# GpsTracker_v1_0.net
KiCad netlist of a schematic drawn in EAGLE
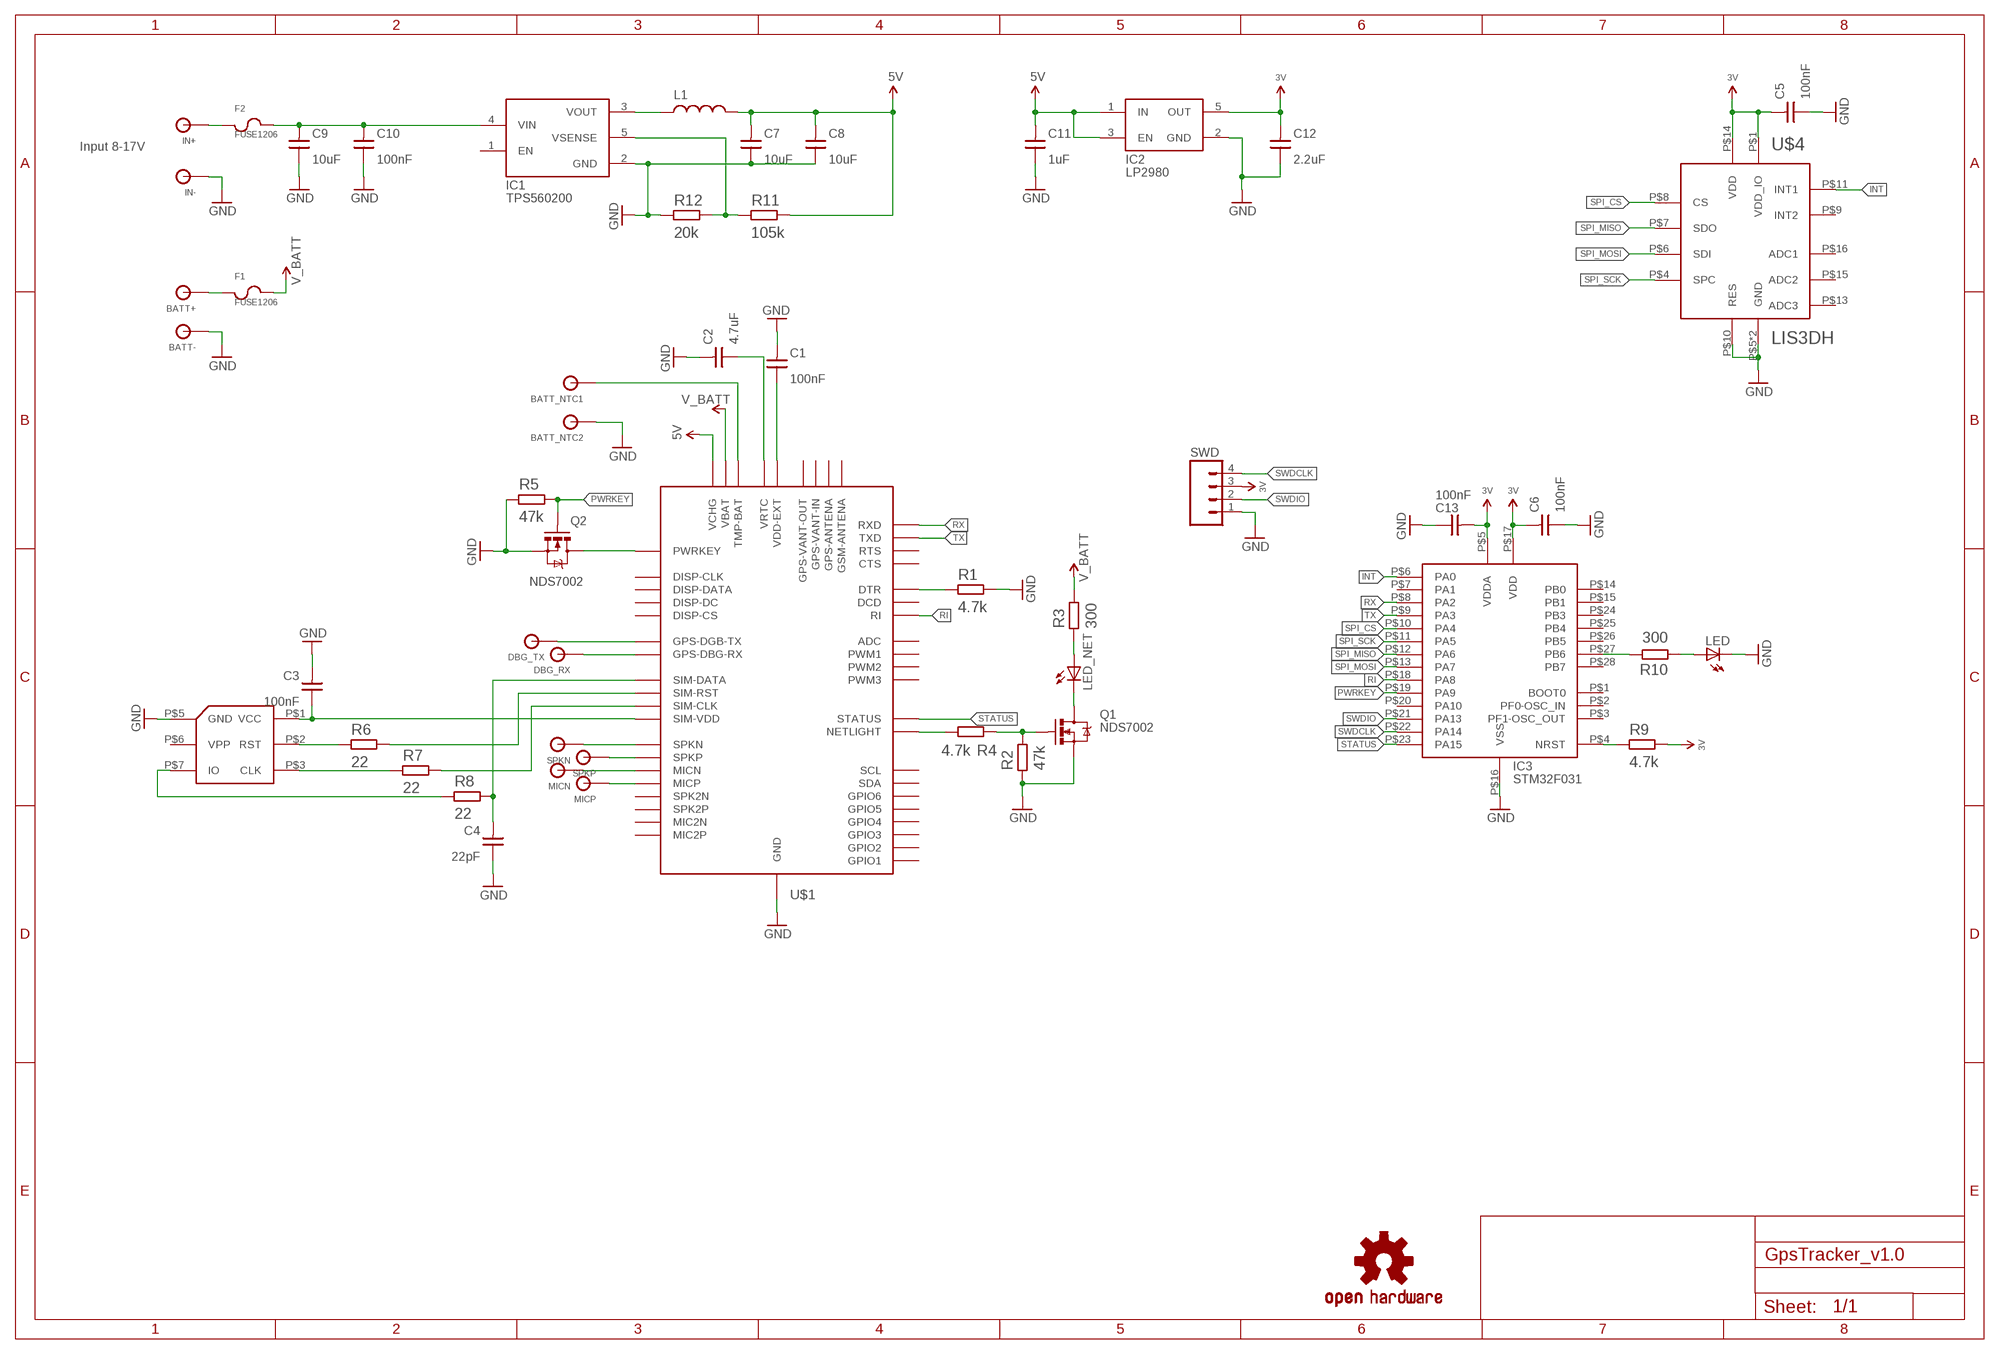
[diagram p0: schematic, sheet 1]

(export (version "E")
  (design (tool "Eeschema 10.0.6"))
  (components
    (comp (ref "BATT+")
      (value "TEST_POINT_SMD")
      (footprint "eagle-import:TEST_POINT_SMD")
      (libsource (lib "eagle-import") (part "TEST_POINT_SMD"))
    )
    (comp (ref "BATT-")
      (value "TEST_POINT_SMD")
      (footprint "eagle-import:TEST_POINT_SMD")
      (libsource (lib "eagle-import") (part "TEST_POINT_SMD"))
    )
    (comp (ref "BATT_NTC1")
      (value "TEST_POINT_R04")
      (footprint "eagle-import:TP_R04")
      (libsource (lib "eagle-import") (part "TEST_POINT_R04"))
    )
    (comp (ref "BATT_NTC2")
      (value "TEST_POINT_R04")
      (footprint "eagle-import:TP_R04")
      (libsource (lib "eagle-import") (part "TEST_POINT_R04"))
    )
    (comp (ref "C1")
      (value "100nF")
      (footprint "eagle-import:R0603")
      (libsource (lib "eagle-import") (part "C0603"))
    )
    (comp (ref "C2")
      (value "4.7uF")
      (footprint "eagle-import:R0805")
      (libsource (lib "eagle-import") (part "C0805"))
    )
    (comp (ref "C3")
      (value "100nF")
      (footprint "eagle-import:R0603")
      (libsource (lib "eagle-import") (part "C0603"))
    )
    (comp (ref "C4")
      (value "22pF")
      (footprint "eagle-import:R0603")
      (libsource (lib "eagle-import") (part "C0603"))
    )
    (comp (ref "C5")
      (value "100nF")
      (footprint "eagle-import:R0603")
      (libsource (lib "eagle-import") (part "C0603"))
    )
    (comp (ref "C6")
      (value "100nF")
      (footprint "eagle-import:R0603")
      (libsource (lib "eagle-import") (part "C0603"))
    )
    (comp (ref "C7")
      (value "10uF")
      (footprint "eagle-import:R0805")
      (libsource (lib "eagle-import") (part "C0805"))
    )
    (comp (ref "C8")
      (value "10uF")
      (footprint "eagle-import:R0805")
      (libsource (lib "eagle-import") (part "C0805"))
    )
    (comp (ref "C9")
      (value "10uF")
      (footprint "eagle-import:1206")
      (libsource (lib "eagle-import") (part "C1206"))
    )
    (comp (ref "C10")
      (value "100nF")
      (footprint "eagle-import:R0603")
      (libsource (lib "eagle-import") (part "C0603"))
    )
    (comp (ref "C11")
      (value "1uF")
      (footprint "eagle-import:R0805")
      (libsource (lib "eagle-import") (part "C0805"))
    )
    (comp (ref "C12")
      (value "2.2uF")
      (footprint "eagle-import:R0805")
      (libsource (lib "eagle-import") (part "C0805"))
    )
    (comp (ref "C13")
      (value "100nF")
      (footprint "eagle-import:R0603")
      (libsource (lib "eagle-import") (part "C0603"))
    )
    (comp (ref "DBG_RX")
      (value "TEST_POINT_R04")
      (footprint "eagle-import:TP_R04")
      (libsource (lib "eagle-import") (part "TEST_POINT_R04"))
    )
    (comp (ref "DBG_TX")
      (value "TEST_POINT_R04")
      (footprint "eagle-import:TP_R04")
      (libsource (lib "eagle-import") (part "TEST_POINT_R04"))
    )
    (comp (ref "F1")
      (value "FUSE1206")
      (footprint "eagle-import:1206")
      (libsource (lib "eagle-import") (part "FUSE1206"))
    )
    (comp (ref "F2")
      (value "FUSE1206")
      (footprint "eagle-import:1206")
      (libsource (lib "eagle-import") (part "FUSE1206"))
    )
    (comp (ref "IC1")
      (value "TPS560200")
      (footprint "eagle-import:SOT23-5L")
      (libsource (lib "eagle-import") (part "TPS560200"))
    )
    (comp (ref "IC2")
      (value "LP2980")
      (footprint "eagle-import:SOT23-5L")
      (libsource (lib "eagle-import") (part "LP2980"))
    )
    (comp (ref "IC3")
      (value "STM32F031")
      (footprint "eagle-import:UFQFPN28")
      (libsource (lib "eagle-import") (part "STM32F031"))
    )
    (comp (ref "IN+")
      (value "TEST_POINT_SMD")
      (footprint "eagle-import:TEST_POINT_SMD")
      (libsource (lib "eagle-import") (part "TEST_POINT_SMD"))
    )
    (comp (ref "IN-")
      (value "TEST_POINT_SMD")
      (footprint "eagle-import:TEST_POINT_SMD")
      (libsource (lib "eagle-import") (part "TEST_POINT_SMD"))
    )
    (comp (ref "L1")
      (value "LNRG_4026")
      (footprint "eagle-import:NRG_4026")
      (libsource (lib "eagle-import") (part "LNRG_4026"))
    )
    (comp (ref "LED")
      (value "LED0603")
      (footprint "eagle-import:LED-0603")
      (libsource (lib "eagle-import") (part "LED0603"))
    )
    (comp (ref "LED_NET")
      (value "LED0603")
      (footprint "eagle-import:LED-0603")
      (libsource (lib "eagle-import") (part "LED0603"))
    )
    (comp (ref "LOGO1")
      (value "OSHW-LOGOS")
      (footprint "eagle-import:OSHW-LOGO-S")
      (libsource (lib "eagle-import") (part "OSHW-LOGOS"))
    )
    (comp (ref "MICN")
      (value "TEST_POINT_R04")
      (footprint "eagle-import:TP_R04")
      (libsource (lib "eagle-import") (part "TEST_POINT_R04"))
    )
    (comp (ref "MICP")
      (value "TEST_POINT_R04")
      (footprint "eagle-import:TP_R04")
      (libsource (lib "eagle-import") (part "TEST_POINT_R04"))
    )
    (comp (ref "Q1")
      (value "NDS7002")
      (footprint "eagle-import:SOT23")
      (libsource (lib "eagle-import") (part "NDS7002"))
    )
    (comp (ref "Q2")
      (value "NDS7002")
      (footprint "eagle-import:SOT23")
      (libsource (lib "eagle-import") (part "NDS7002"))
    )
    (comp (ref "R1")
      (value "4.7k")
      (footprint "eagle-import:R0603")
      (libsource (lib "eagle-import") (part "R0603"))
    )
    (comp (ref "R2")
      (value "47k")
      (footprint "eagle-import:R0603")
      (libsource (lib "eagle-import") (part "R0603"))
    )
    (comp (ref "R3")
      (value "300")
      (footprint "eagle-import:R0603")
      (libsource (lib "eagle-import") (part "R0603"))
    )
    (comp (ref "R4")
      (value "4.7k")
      (footprint "eagle-import:R0603")
      (libsource (lib "eagle-import") (part "R0603"))
    )
    (comp (ref "R5")
      (value "47k")
      (footprint "eagle-import:R0603")
      (libsource (lib "eagle-import") (part "R0603"))
    )
    (comp (ref "R6")
      (value "22")
      (footprint "eagle-import:R0603")
      (libsource (lib "eagle-import") (part "R0603"))
    )
    (comp (ref "R7")
      (value "22")
      (footprint "eagle-import:R0603")
      (libsource (lib "eagle-import") (part "R0603"))
    )
    (comp (ref "R8")
      (value "22")
      (footprint "eagle-import:R0603")
      (libsource (lib "eagle-import") (part "R0603"))
    )
    (comp (ref "R9")
      (value "4.7k")
      (footprint "eagle-import:R0603")
      (libsource (lib "eagle-import") (part "R0603"))
    )
    (comp (ref "R10")
      (value "300")
      (footprint "eagle-import:R0603")
      (libsource (lib "eagle-import") (part "R0603"))
    )
    (comp (ref "R11")
      (value "105k")
      (footprint "eagle-import:R0603")
      (libsource (lib "eagle-import") (part "R0603"))
    )
    (comp (ref "R12")
      (value "20k")
      (footprint "eagle-import:R0603")
      (libsource (lib "eagle-import") (part "R0603"))
    )
    (comp (ref "SPKN")
      (value "TEST_POINT_R04")
      (footprint "eagle-import:TP_R04")
      (libsource (lib "eagle-import") (part "TEST_POINT_R04"))
    )
    (comp (ref "SPKP")
      (value "TEST_POINT_R04")
      (footprint "eagle-import:TP_R04")
      (libsource (lib "eagle-import") (part "TEST_POINT_R04"))
    )
    (comp (ref "SWD")
      (value "M041.27MM")
      (footprint "eagle-import:1X04-1.27MM")
      (libsource (lib "eagle-import") (part "M041.27MM"))
    )
    (comp (ref "U$1")
      (value "SIM908")
      (footprint "eagle-import:SIM908")
      (libsource (lib "eagle-import") (part "SIM908"))
    )
    (comp (ref "U$3")
      (value "SIM_CARD")
      (footprint "eagle-import:SIM_SAMSUNG")
      (libsource (lib "eagle-import") (part "SIM_CARD"))
    )
    (comp (ref "U$4")
      (value "LIS3DH")
      (footprint "eagle-import:LGA16D")
      (libsource (lib "eagle-import") (part "LIS3DH"))
    )
  )
  (nets
    (net (code "1") (name "3V") (class "Default")
      (node (ref "C12") (pin "2") (pinfunction "2_2") (pintype "bidirectional"))
      (node (ref "C13") (pin "2") (pinfunction "2_2") (pintype "bidirectional"))
      (node (ref "C5") (pin "2") (pinfunction "2_2") (pintype "bidirectional"))
      (node (ref "C6") (pin "2") (pinfunction "2_2") (pintype "bidirectional"))
      (node (ref "IC2") (pin "5") (pinfunction "OUT_5") (pintype "bidirectional"))
      (node (ref "IC3") (pin "P$17") (pinfunction "VDD_P$17") (pintype "bidirectional"))
      (node (ref "IC3") (pin "P$5") (pinfunction "VDDA_P$5") (pintype "bidirectional"))
      (node (ref "R9") (pin "2") (pinfunction "2_2") (pintype "bidirectional"))
      (node (ref "SWD") (pin "3") (pinfunction "3_3") (pintype "passive"))
      (node (ref "U$4") (pin "P$1") (pinfunction "VDD_IO_P$1") (pintype "bidirectional"))
      (node (ref "U$4") (pin "P$14") (pinfunction "VDD_P$14") (pintype "bidirectional"))
    )
    (net (code "2") (name "5V") (class "Default")
      (node (ref "C11") (pin "2") (pinfunction "2_2") (pintype "bidirectional"))
      (node (ref "C7") (pin "2") (pinfunction "2_2") (pintype "bidirectional"))
      (node (ref "C8") (pin "2") (pinfunction "2_2") (pintype "bidirectional"))
      (node (ref "IC2") (pin "1") (pinfunction "IN_1") (pintype "bidirectional"))
      (node (ref "IC2") (pin "3") (pinfunction "EN_3") (pintype "bidirectional"))
      (node (ref "L1") (pin "P$2") (pinfunction "2_P$2") (pintype "bidirectional"))
      (node (ref "R11") (pin "2") (pinfunction "2_2") (pintype "bidirectional"))
      (node (ref "U$1") (pin "VCHG") (pinfunction "VCHG_VCHG") (pintype "bidirectional"))
    )
    (net (code "3") (name "GND") (class "Default")
      (node (ref "BATT-") (pin "P$1") (pinfunction "P$1_P$1") (pintype "bidirectional"))
      (node (ref "BATT_NTC2") (pin "P$1") (pinfunction "P$1_P$1") (pintype "bidirectional"))
      (node (ref "C1") (pin "2") (pinfunction "2_2") (pintype "bidirectional"))
      (node (ref "C10") (pin "1") (pinfunction "1_1") (pintype "bidirectional"))
      (node (ref "C11") (pin "1") (pinfunction "1_1") (pintype "bidirectional"))
      (node (ref "C12") (pin "1") (pinfunction "1_1") (pintype "bidirectional"))
      (node (ref "C13") (pin "1") (pinfunction "1_1") (pintype "bidirectional"))
      (node (ref "C2") (pin "2") (pinfunction "2_2") (pintype "bidirectional"))
      (node (ref "C3") (pin "2") (pinfunction "2_2") (pintype "bidirectional"))
      (node (ref "C4") (pin "1") (pinfunction "1_1") (pintype "bidirectional"))
      (node (ref "C5") (pin "1") (pinfunction "1_1") (pintype "bidirectional"))
      (node (ref "C6") (pin "1") (pinfunction "1_1") (pintype "bidirectional"))
      (node (ref "C7") (pin "1") (pinfunction "1_1") (pintype "bidirectional"))
      (node (ref "C8") (pin "1") (pinfunction "1_1") (pintype "bidirectional"))
      (node (ref "C9") (pin "1") (pinfunction "1_1") (pintype "bidirectional"))
      (node (ref "IC1") (pin "2") (pinfunction "GND_2") (pintype "bidirectional"))
      (node (ref "IC2") (pin "2") (pinfunction "GND_2") (pintype "bidirectional"))
      (node (ref "IC3") (pin "P$16") (pinfunction "VSS_P$16") (pintype "bidirectional"))
      (node (ref "IN-") (pin "P$1") (pinfunction "P$1_P$1") (pintype "bidirectional"))
      (node (ref "LED") (pin "C") (pinfunction "C_C") (pintype "passive"))
      (node (ref "Q1") (pin "2") (pinfunction "S_2") (pintype "passive"))
      (node (ref "Q2") (pin "2") (pinfunction "S_2") (pintype "passive"))
      (node (ref "R1") (pin "2") (pinfunction "2_2") (pintype "bidirectional"))
      (node (ref "R12") (pin "1") (pinfunction "1_1") (pintype "bidirectional"))
      (node (ref "R2") (pin "1") (pinfunction "1_1") (pintype "bidirectional"))
      (node (ref "R5") (pin "1") (pinfunction "1_1") (pintype "bidirectional"))
      (node (ref "SWD") (pin "1") (pinfunction "1_1") (pintype "passive"))
      (node (ref "U$1") (pin "GND") (pinfunction "GND_GND") (pintype "bidirectional"))
      (node (ref "U$1") (pin "GND10") (pinfunction "GND_GND10") (pintype "bidirectional"))
      (node (ref "U$1") (pin "GND11") (pinfunction "GND_GND11") (pintype "bidirectional"))
      (node (ref "U$1") (pin "GND12") (pinfunction "GND_GND12") (pintype "bidirectional"))
      (node (ref "U$1") (pin "GND13") (pinfunction "GND_GND13") (pintype "bidirectional"))
      (node (ref "U$1") (pin "GND14") (pinfunction "GND_GND14") (pintype "bidirectional"))
      (node (ref "U$1") (pin "GND15") (pinfunction "GND_GND15") (pintype "bidirectional"))
      (node (ref "U$1") (pin "GND16") (pinfunction "GND_GND16") (pintype "bidirectional"))
      (node (ref "U$1") (pin "GND17") (pinfunction "GND_GND17") (pintype "bidirectional"))
      (node (ref "U$1") (pin "GND18") (pinfunction "GND_GND18") (pintype "bidirectional"))
      (node (ref "U$1") (pin "GND2") (pinfunction "GND_GND2") (pintype "bidirectional"))
      (node (ref "U$1") (pin "GND3") (pinfunction "GND_GND3") (pintype "bidirectional"))
      (node (ref "U$1") (pin "GND4") (pinfunction "GND_GND4") (pintype "bidirectional"))
      (node (ref "U$1") (pin "GND5") (pinfunction "GND_GND5") (pintype "bidirectional"))
      (node (ref "U$1") (pin "GND6") (pinfunction "GND_GND6") (pintype "bidirectional"))
      (node (ref "U$1") (pin "GND7") (pinfunction "GND_GND7") (pintype "bidirectional"))
      (node (ref "U$1") (pin "GND8") (pinfunction "GND_GND8") (pintype "bidirectional"))
      (node (ref "U$1") (pin "GND9") (pinfunction "GND_GND9") (pintype "bidirectional"))
      (node (ref "U$3") (pin "P$5") (pinfunction "GND_P$5") (pintype "bidirectional"))
      (node (ref "U$4") (pin "P$10") (pinfunction "RES_P$10") (pintype "bidirectional"))
      (node (ref "U$4") (pin "P$12") (pinfunction "GND_P$12") (pintype "bidirectional"))
      (node (ref "U$4") (pin "P$5") (pinfunction "GND_P$5") (pintype "bidirectional"))
    )
    (net (code "4") (name "INT") (class "Default")
      (node (ref "IC3") (pin "P$6") (pinfunction "PA0_P$6") (pintype "bidirectional"))
      (node (ref "U$4") (pin "P$11") (pinfunction "INT1_P$11") (pintype "bidirectional"))
    )
    (net (code "5") (name "Net-(BATT+-PadP$1)") (class "Default")
      (node (ref "BATT+") (pin "P$1") (pinfunction "P$1_P$1") (pintype "bidirectional"))
      (node (ref "F1") (pin "1") (pinfunction "1_1") (pintype "bidirectional"))
    )
    (net (code "6") (name "Net-(C1-Pad1)") (class "Default")
      (node (ref "C1") (pin "1") (pinfunction "1_1") (pintype "bidirectional"))
      (node (ref "U$1") (pin "VDD-EXT") (pinfunction "VDD-EXT_VDD-EXT") (pintype "bidirectional"))
    )
    (net (code "7") (name "Net-(C2-Pad1)") (class "Default")
      (node (ref "C2") (pin "1") (pinfunction "1_1") (pintype "bidirectional"))
      (node (ref "U$1") (pin "VRTC") (pinfunction "VRTC_VRTC") (pintype "bidirectional"))
    )
    (net (code "8") (name "Net-(C4-Pad2)") (class "Default")
      (node (ref "C4") (pin "2") (pinfunction "2_2") (pintype "bidirectional"))
      (node (ref "R8") (pin "2") (pinfunction "2_2") (pintype "bidirectional"))
      (node (ref "U$1") (pin "SIM-DATA") (pinfunction "SIM-DATA_SIM-DATA") (pintype "bidirectional"))
    )
    (net (code "9") (name "Net-(F2-Pad1)") (class "Default")
      (node (ref "F2") (pin "1") (pinfunction "1_1") (pintype "bidirectional"))
      (node (ref "IN+") (pin "P$1") (pinfunction "P$1_P$1") (pintype "bidirectional"))
    )
    (net (code "10") (name "Net-(IC1-VIN)") (class "Default")
      (node (ref "C10") (pin "2") (pinfunction "2_2") (pintype "bidirectional"))
      (node (ref "C9") (pin "2") (pinfunction "2_2") (pintype "bidirectional"))
      (node (ref "F2") (pin "2") (pinfunction "2_2") (pintype "bidirectional"))
      (node (ref "IC1") (pin "4") (pinfunction "VIN_4") (pintype "bidirectional"))
    )
    (net (code "11") (name "Net-(IC1-VOUT)") (class "Default")
      (node (ref "IC1") (pin "3") (pinfunction "VOUT_3") (pintype "bidirectional"))
      (node (ref "L1") (pin "P$1") (pinfunction "1_P$1") (pintype "bidirectional"))
    )
    (net (code "12") (name "Net-(IC1-VSENSE)") (class "Default")
      (node (ref "IC1") (pin "5") (pinfunction "VSENSE_5") (pintype "bidirectional"))
      (node (ref "R11") (pin "1") (pinfunction "1_1") (pintype "bidirectional"))
      (node (ref "R12") (pin "2") (pinfunction "2_2") (pintype "bidirectional"))
    )
    (net (code "13") (name "Net-(IC3-NRST)") (class "Default")
      (node (ref "IC3") (pin "P$4") (pinfunction "NRST_P$4") (pintype "bidirectional"))
      (node (ref "R9") (pin "1") (pinfunction "1_1") (pintype "bidirectional"))
    )
    (net (code "14") (name "Net-(IC3-PB6)") (class "Default")
      (node (ref "IC3") (pin "P$27") (pinfunction "PB6_P$27") (pintype "bidirectional"))
      (node (ref "R10") (pin "2") (pinfunction "2_2") (pintype "bidirectional"))
    )
    (net (code "15") (name "Net-(LED-PadA)") (class "Default")
      (node (ref "LED") (pin "A") (pinfunction "A_A") (pintype "passive"))
      (node (ref "R10") (pin "1") (pinfunction "1_1") (pintype "bidirectional"))
    )
    (net (code "16") (name "Net-(LED_NET-PadA)") (class "Default")
      (node (ref "LED_NET") (pin "A") (pinfunction "A_A") (pintype "passive"))
      (node (ref "R3") (pin "1") (pinfunction "1_1") (pintype "bidirectional"))
    )
    (net (code "17") (name "Net-(Q1-D)") (class "Default")
      (node (ref "LED_NET") (pin "C") (pinfunction "C_C") (pintype "passive"))
      (node (ref "Q1") (pin "3") (pinfunction "D_3") (pintype "passive"))
    )
    (net (code "18") (name "Net-(Q1-G)") (class "Default")
      (node (ref "Q1") (pin "1") (pinfunction "G_1") (pintype "passive"))
      (node (ref "R2") (pin "2") (pinfunction "2_2") (pintype "bidirectional"))
      (node (ref "R4") (pin "1") (pinfunction "1_1") (pintype "bidirectional"))
    )
    (net (code "19") (name "Net-(Q2-D)") (class "Default")
      (node (ref "Q2") (pin "3") (pinfunction "D_3") (pintype "passive"))
      (node (ref "U$1") (pin "PWRKEY") (pinfunction "PWRKEY_PWRKEY") (pintype "bidirectional"))
    )
    (net (code "20") (name "Net-(R1-Pad1)") (class "Default")
      (node (ref "R1") (pin "1") (pinfunction "1_1") (pintype "bidirectional"))
      (node (ref "U$1") (pin "DTR") (pinfunction "DTR_DTR") (pintype "bidirectional"))
    )
    (net (code "21") (name "Net-(R4-Pad2)") (class "Default")
      (node (ref "R4") (pin "2") (pinfunction "2_2") (pintype "bidirectional"))
      (node (ref "U$1") (pin "NETLIGHT") (pinfunction "NETLIGHT_NETLIGHT") (pintype "bidirectional"))
    )
    (net (code "22") (name "Net-(R6-Pad2)") (class "Default")
      (node (ref "R6") (pin "2") (pinfunction "2_2") (pintype "bidirectional"))
      (node (ref "U$1") (pin "SIM-RST") (pinfunction "SIM-RST_SIM-RST") (pintype "bidirectional"))
    )
    (net (code "23") (name "Net-(R7-Pad2)") (class "Default")
      (node (ref "R7") (pin "2") (pinfunction "2_2") (pintype "bidirectional"))
      (node (ref "U$1") (pin "SIM-CLK") (pinfunction "SIM-CLK_SIM-CLK") (pintype "bidirectional"))
    )
    (net (code "24") (name "Net-(U$1-GPS-DBG-RX)") (class "Default")
      (node (ref "DBG_RX") (pin "P$1") (pinfunction "P$1_P$1") (pintype "bidirectional"))
      (node (ref "U$1") (pin "GPS-DBG-RXD") (pinfunction "GPS-DBG-RX_GPS-DBG-RXD") (pintype "bidirectional"))
    )
    (net (code "25") (name "Net-(U$1-GPS-DGB-TX)") (class "Default")
      (node (ref "DBG_TX") (pin "P$1") (pinfunction "P$1_P$1") (pintype "bidirectional"))
      (node (ref "U$1") (pin "GPS-DBG-TXD") (pinfunction "GPS-DGB-TX_GPS-DBG-TXD") (pintype "bidirectional"))
    )
    (net (code "26") (name "Net-(U$1-MICN)") (class "Default")
      (node (ref "MICN") (pin "P$1") (pinfunction "P$1_P$1") (pintype "bidirectional"))
      (node (ref "U$1") (pin "MIC1N") (pinfunction "MICN_MIC1N") (pintype "bidirectional"))
    )
    (net (code "27") (name "Net-(U$1-MICP)") (class "Default")
      (node (ref "MICP") (pin "P$1") (pinfunction "P$1_P$1") (pintype "bidirectional"))
      (node (ref "U$1") (pin "MIC1P") (pinfunction "MICP_MIC1P") (pintype "bidirectional"))
    )
    (net (code "28") (name "Net-(U$1-SPKN)") (class "Default")
      (node (ref "SPKN") (pin "P$1") (pinfunction "P$1_P$1") (pintype "bidirectional"))
      (node (ref "U$1") (pin "SPK1N") (pinfunction "SPKN_SPK1N") (pintype "bidirectional"))
    )
    (net (code "29") (name "Net-(U$1-SPKP)") (class "Default")
      (node (ref "SPKP") (pin "P$1") (pinfunction "P$1_P$1") (pintype "bidirectional"))
      (node (ref "U$1") (pin "SPK1P") (pinfunction "SPKP_SPK1P") (pintype "bidirectional"))
    )
    (net (code "30") (name "Net-(U$1-TMP-BAT)") (class "Default")
      (node (ref "BATT_NTC1") (pin "P$1") (pinfunction "P$1_P$1") (pintype "bidirectional"))
      (node (ref "U$1") (pin "TEMP-BAT") (pinfunction "TMP-BAT_TEMP-BAT") (pintype "bidirectional"))
    )
    (net (code "31") (name "Net-(U$3-CLK)") (class "Default")
      (node (ref "R7") (pin "1") (pinfunction "1_1") (pintype "bidirectional"))
      (node (ref "U$3") (pin "P$3") (pinfunction "CLK_P$3") (pintype "bidirectional"))
    )
    (net (code "32") (name "Net-(U$3-IO)") (class "Default")
      (node (ref "R8") (pin "1") (pinfunction "1_1") (pintype "bidirectional"))
      (node (ref "U$3") (pin "P$7") (pinfunction "IO_P$7") (pintype "bidirectional"))
    )
    (net (code "33") (name "Net-(U$3-RST)") (class "Default")
      (node (ref "R6") (pin "1") (pinfunction "1_1") (pintype "bidirectional"))
      (node (ref "U$3") (pin "P$2") (pinfunction "RST_P$2") (pintype "bidirectional"))
    )
    (net (code "34") (name "Net-(U$3-VCC)") (class "Default")
      (node (ref "C3") (pin "1") (pinfunction "1_1") (pintype "bidirectional"))
      (node (ref "U$1") (pin "SIM-VDD") (pinfunction "SIM-VDD_SIM-VDD") (pintype "bidirectional"))
      (node (ref "U$3") (pin "P$1") (pinfunction "VCC_P$1") (pintype "bidirectional"))
    )
    (net (code "35") (name "PWRKEY") (class "Default")
      (node (ref "IC3") (pin "P$19") (pinfunction "PA9_P$19") (pintype "bidirectional"))
      (node (ref "Q2") (pin "1") (pinfunction "G_1") (pintype "passive"))
      (node (ref "R5") (pin "2") (pinfunction "2_2") (pintype "bidirectional"))
    )
    (net (code "36") (name "RI") (class "Default")
      (node (ref "IC3") (pin "P$18") (pinfunction "PA8_P$18") (pintype "bidirectional"))
      (node (ref "U$1") (pin "RI") (pinfunction "RI_RI") (pintype "bidirectional"))
    )
    (net (code "37") (name "RX") (class "Default")
      (node (ref "IC3") (pin "P$8") (pinfunction "PA2_P$8") (pintype "bidirectional"))
      (node (ref "U$1") (pin "RXD") (pinfunction "RXD_RXD") (pintype "bidirectional"))
    )
    (net (code "38") (name "SPI_CS") (class "Default")
      (node (ref "IC3") (pin "P$10") (pinfunction "PA4_P$10") (pintype "bidirectional"))
      (node (ref "U$4") (pin "P$8") (pinfunction "CS_P$8") (pintype "bidirectional"))
    )
    (net (code "39") (name "SPI_MISO") (class "Default")
      (node (ref "IC3") (pin "P$12") (pinfunction "PA6_P$12") (pintype "bidirectional"))
      (node (ref "U$4") (pin "P$7") (pinfunction "SDO_P$7") (pintype "bidirectional"))
    )
    (net (code "40") (name "SPI_MOSI") (class "Default")
      (node (ref "IC3") (pin "P$13") (pinfunction "PA7_P$13") (pintype "bidirectional"))
      (node (ref "U$4") (pin "P$6") (pinfunction "SDI_P$6") (pintype "bidirectional"))
    )
    (net (code "41") (name "SPI_SCK") (class "Default")
      (node (ref "IC3") (pin "P$11") (pinfunction "PA5_P$11") (pintype "bidirectional"))
      (node (ref "U$4") (pin "P$4") (pinfunction "SPC_P$4") (pintype "bidirectional"))
    )
    (net (code "42") (name "STATUS") (class "Default")
      (node (ref "IC3") (pin "P$23") (pinfunction "PA15_P$23") (pintype "bidirectional"))
      (node (ref "U$1") (pin "STATUS") (pinfunction "STATUS_STATUS") (pintype "bidirectional"))
    )
    (net (code "43") (name "SWDCLK") (class "Default")
      (node (ref "IC3") (pin "P$22") (pinfunction "PA14_P$22") (pintype "bidirectional"))
      (node (ref "SWD") (pin "4") (pinfunction "4_4") (pintype "passive"))
    )
    (net (code "44") (name "SWDIO") (class "Default")
      (node (ref "IC3") (pin "P$21") (pinfunction "PA13_P$21") (pintype "bidirectional"))
      (node (ref "SWD") (pin "2") (pinfunction "2_2") (pintype "passive"))
    )
    (net (code "45") (name "TX") (class "Default")
      (node (ref "IC3") (pin "P$9") (pinfunction "PA3_P$9") (pintype "bidirectional"))
      (node (ref "U$1") (pin "TXD") (pinfunction "TXD_TXD") (pintype "bidirectional"))
    )
    (net (code "46") (name "V_BATT") (class "Default")
      (node (ref "F1") (pin "2") (pinfunction "2_2") (pintype "bidirectional"))
      (node (ref "R3") (pin "2") (pinfunction "2_2") (pintype "bidirectional"))
      (node (ref "U$1") (pin "VBAT") (pinfunction "VBAT_VBAT") (pintype "bidirectional"))
      (node (ref "U$1") (pin "VBAT2") (pinfunction "VBAT_VBAT2") (pintype "bidirectional"))
    )
    (net (code "47") (name "unconnected-(IC1-EN-Pad1)") (class "Default")
      (node (ref "IC1") (pin "1") (pinfunction "EN_1") (pintype "bidirectional"))
    )
    (net (code "48") (name "unconnected-(IC3-BOOT0-PadP$1)") (class "Default")
      (node (ref "IC3") (pin "P$1") (pinfunction "BOOT0_P$1") (pintype "bidirectional"))
    )
    (net (code "49") (name "unconnected-(IC3-PA1-PadP$7)") (class "Default")
      (node (ref "IC3") (pin "P$7") (pinfunction "PA1_P$7") (pintype "bidirectional"))
    )
    (net (code "50") (name "unconnected-(IC3-PA10-PadP$20)") (class "Default")
      (node (ref "IC3") (pin "P$20") (pinfunction "PA10_P$20") (pintype "bidirectional"))
    )
    (net (code "51") (name "unconnected-(IC3-PB0-PadP$14)") (class "Default")
      (node (ref "IC3") (pin "P$14") (pinfunction "PB0_P$14") (pintype "bidirectional"))
    )
    (net (code "52") (name "unconnected-(IC3-PB1-PadP$15)") (class "Default")
      (node (ref "IC3") (pin "P$15") (pinfunction "PB1_P$15") (pintype "bidirectional"))
    )
    (net (code "53") (name "unconnected-(IC3-PB3-PadP$24)") (class "Default")
      (node (ref "IC3") (pin "P$24") (pinfunction "PB3_P$24") (pintype "bidirectional"))
    )
    (net (code "54") (name "unconnected-(IC3-PB4-PadP$25)") (class "Default")
      (node (ref "IC3") (pin "P$25") (pinfunction "PB4_P$25") (pintype "bidirectional"))
    )
    (net (code "55") (name "unconnected-(IC3-PB5-PadP$26)") (class "Default")
      (node (ref "IC3") (pin "P$26") (pinfunction "PB5_P$26") (pintype "bidirectional"))
    )
    (net (code "56") (name "unconnected-(IC3-PB7-PadP$28)") (class "Default")
      (node (ref "IC3") (pin "P$28") (pinfunction "PB7_P$28") (pintype "bidirectional"))
    )
    (net (code "57") (name "unconnected-(IC3-PF0-OSC_IN-PadP$2)") (class "Default")
      (node (ref "IC3") (pin "P$2") (pinfunction "PF0-OSC_IN_P$2") (pintype "bidirectional"))
    )
    (net (code "58") (name "unconnected-(IC3-PF1-OSC_OUT-PadP$3)") (class "Default")
      (node (ref "IC3") (pin "P$3") (pinfunction "PF1-OSC_OUT_P$3") (pintype "bidirectional"))
    )
    (net (code "59") (name "unconnected-(U$1-PadADC)") (class "Default")
      (node (ref "U$1") (pin "ADC") (pinfunction "ADC_ADC") (pintype "bidirectional"))
    )
    (net (code "60") (name "unconnected-(U$1-PadCTS)") (class "Default")
      (node (ref "U$1") (pin "CTS") (pinfunction "CTS_CTS") (pintype "bidirectional"))
    )
    (net (code "61") (name "unconnected-(U$1-PadDCD)") (class "Default")
      (node (ref "U$1") (pin "DCD") (pinfunction "DCD_DCD") (pintype "bidirectional"))
    )
    (net (code "62") (name "unconnected-(U$1-PadDISP-CLK)") (class "Default")
      (node (ref "U$1") (pin "DISP-CLK") (pinfunction "DISP-CLK_DISP-CLK") (pintype "bidirectional"))
    )
    (net (code "63") (name "unconnected-(U$1-PadDISP-CS)") (class "Default")
      (node (ref "U$1") (pin "DISP-CS") (pinfunction "DISP-CS_DISP-CS") (pintype "bidirectional"))
    )
    (net (code "64") (name "unconnected-(U$1-PadDISP-DATA)") (class "Default")
      (node (ref "U$1") (pin "DISP-DATA") (pinfunction "DISP-DATA_DISP-DATA") (pintype "bidirectional"))
    )
    (net (code "65") (name "unconnected-(U$1-PadDISP-DC)") (class "Default")
      (node (ref "U$1") (pin "DISP-DC") (pinfunction "DISP-DC_DISP-DC") (pintype "bidirectional"))
    )
    (net (code "66") (name "unconnected-(U$1-PadGPIO1)") (class "Default")
      (node (ref "U$1") (pin "GPIO1") (pinfunction "GPIO1_GPIO1") (pintype "bidirectional"))
    )
    (net (code "67") (name "unconnected-(U$1-PadGPIO2)") (class "Default")
      (node (ref "U$1") (pin "GPIO2") (pinfunction "GPIO2_GPIO2") (pintype "bidirectional"))
    )
    (net (code "68") (name "unconnected-(U$1-PadGPIO3)") (class "Default")
      (node (ref "U$1") (pin "GPIO3") (pinfunction "GPIO3_GPIO3") (pintype "bidirectional"))
    )
    (net (code "69") (name "unconnected-(U$1-PadGPIO4)") (class "Default")
      (node (ref "U$1") (pin "GPIO4") (pinfunction "GPIO4_GPIO4") (pintype "bidirectional"))
    )
    (net (code "70") (name "unconnected-(U$1-PadGPIO5)") (class "Default")
      (node (ref "U$1") (pin "GPIO5") (pinfunction "GPIO5_GPIO5") (pintype "bidirectional"))
    )
    (net (code "71") (name "unconnected-(U$1-PadGPIO6)") (class "Default")
      (node (ref "U$1") (pin "GPIO6") (pinfunction "GPIO6_GPIO6") (pintype "bidirectional"))
    )
    (net (code "72") (name "unconnected-(U$1-PadGPS-ANTENA)") (class "Default")
      (node (ref "U$1") (pin "GPS-ANTENA") (pinfunction "GPS-ANTENA_GPS-ANTENA") (pintype "bidirectional"))
    )
    (net (code "73") (name "unconnected-(U$1-PadGPS-VANT-IN)") (class "Default")
      (node (ref "U$1") (pin "GPS-VANT-IN") (pinfunction "GPS-VANT-IN_GPS-VANT-IN") (pintype "bidirectional"))
    )
    (net (code "74") (name "unconnected-(U$1-PadGPS-VANT-OUT)") (class "Default")
      (node (ref "U$1") (pin "GPS-VANT-OUT") (pinfunction "GPS-VANT-OUT_GPS-VANT-OUT") (pintype "bidirectional"))
    )
    (net (code "75") (name "unconnected-(U$1-PadGSM-ANTENA)") (class "Default")
      (node (ref "U$1") (pin "GSM-ANTENA") (pinfunction "GSM-ANTENA_GSM-ANTENA") (pintype "bidirectional"))
    )
    (net (code "76") (name "unconnected-(U$1-PadMIC2N)") (class "Default")
      (node (ref "U$1") (pin "MIC2N") (pinfunction "MIC2N_MIC2N") (pintype "bidirectional"))
    )
    (net (code "77") (name "unconnected-(U$1-PadMIC2P)") (class "Default")
      (node (ref "U$1") (pin "MIC2P") (pinfunction "MIC2P_MIC2P") (pintype "bidirectional"))
    )
    (net (code "78") (name "unconnected-(U$1-PadPWM1)") (class "Default")
      (node (ref "U$1") (pin "PWM1") (pinfunction "PWM1_PWM1") (pintype "bidirectional"))
    )
    (net (code "79") (name "unconnected-(U$1-PadPWM2)") (class "Default")
      (node (ref "U$1") (pin "PWM2") (pinfunction "PWM2_PWM2") (pintype "bidirectional"))
    )
    (net (code "80") (name "unconnected-(U$1-PadPWM3)") (class "Default")
      (node (ref "U$1") (pin "PWM3") (pinfunction "PWM3_PWM3") (pintype "bidirectional"))
    )
    (net (code "81") (name "unconnected-(U$1-PadRTS)") (class "Default")
      (node (ref "U$1") (pin "RTS") (pinfunction "RTS_RTS") (pintype "bidirectional"))
    )
    (net (code "82") (name "unconnected-(U$1-PadSCL)") (class "Default")
      (node (ref "U$1") (pin "SCL") (pinfunction "SCL_SCL") (pintype "bidirectional"))
    )
    (net (code "83") (name "unconnected-(U$1-PadSDA)") (class "Default")
      (node (ref "U$1") (pin "SDA") (pinfunction "SDA_SDA") (pintype "bidirectional"))
    )
    (net (code "84") (name "unconnected-(U$1-PadSPK2N)") (class "Default")
      (node (ref "U$1") (pin "SPK2N") (pinfunction "SPK2N_SPK2N") (pintype "bidirectional"))
    )
    (net (code "85") (name "unconnected-(U$1-PadSPK2P)") (class "Default")
      (node (ref "U$1") (pin "SPK2P") (pinfunction "SPK2P_SPK2P") (pintype "bidirectional"))
    )
    (net (code "86") (name "unconnected-(U$3-VPP-PadP$6)") (class "Default")
      (node (ref "U$3") (pin "P$6") (pinfunction "VPP_P$6") (pintype "bidirectional"))
    )
    (net (code "87") (name "unconnected-(U$4-ADC1-PadP$16)") (class "Default")
      (node (ref "U$4") (pin "P$16") (pinfunction "ADC1_P$16") (pintype "bidirectional"))
    )
    (net (code "88") (name "unconnected-(U$4-ADC2-PadP$15)") (class "Default")
      (node (ref "U$4") (pin "P$15") (pinfunction "ADC2_P$15") (pintype "bidirectional"))
    )
    (net (code "89") (name "unconnected-(U$4-ADC3-PadP$13)") (class "Default")
      (node (ref "U$4") (pin "P$13") (pinfunction "ADC3_P$13") (pintype "bidirectional"))
    )
    (net (code "90") (name "unconnected-(U$4-INT2-PadP$9)") (class "Default")
      (node (ref "U$4") (pin "P$9") (pinfunction "INT2_P$9") (pintype "bidirectional"))
    )
  )
)
